# Sheet2.net
KiCad netlist of a schematic drawn in Altium Designer
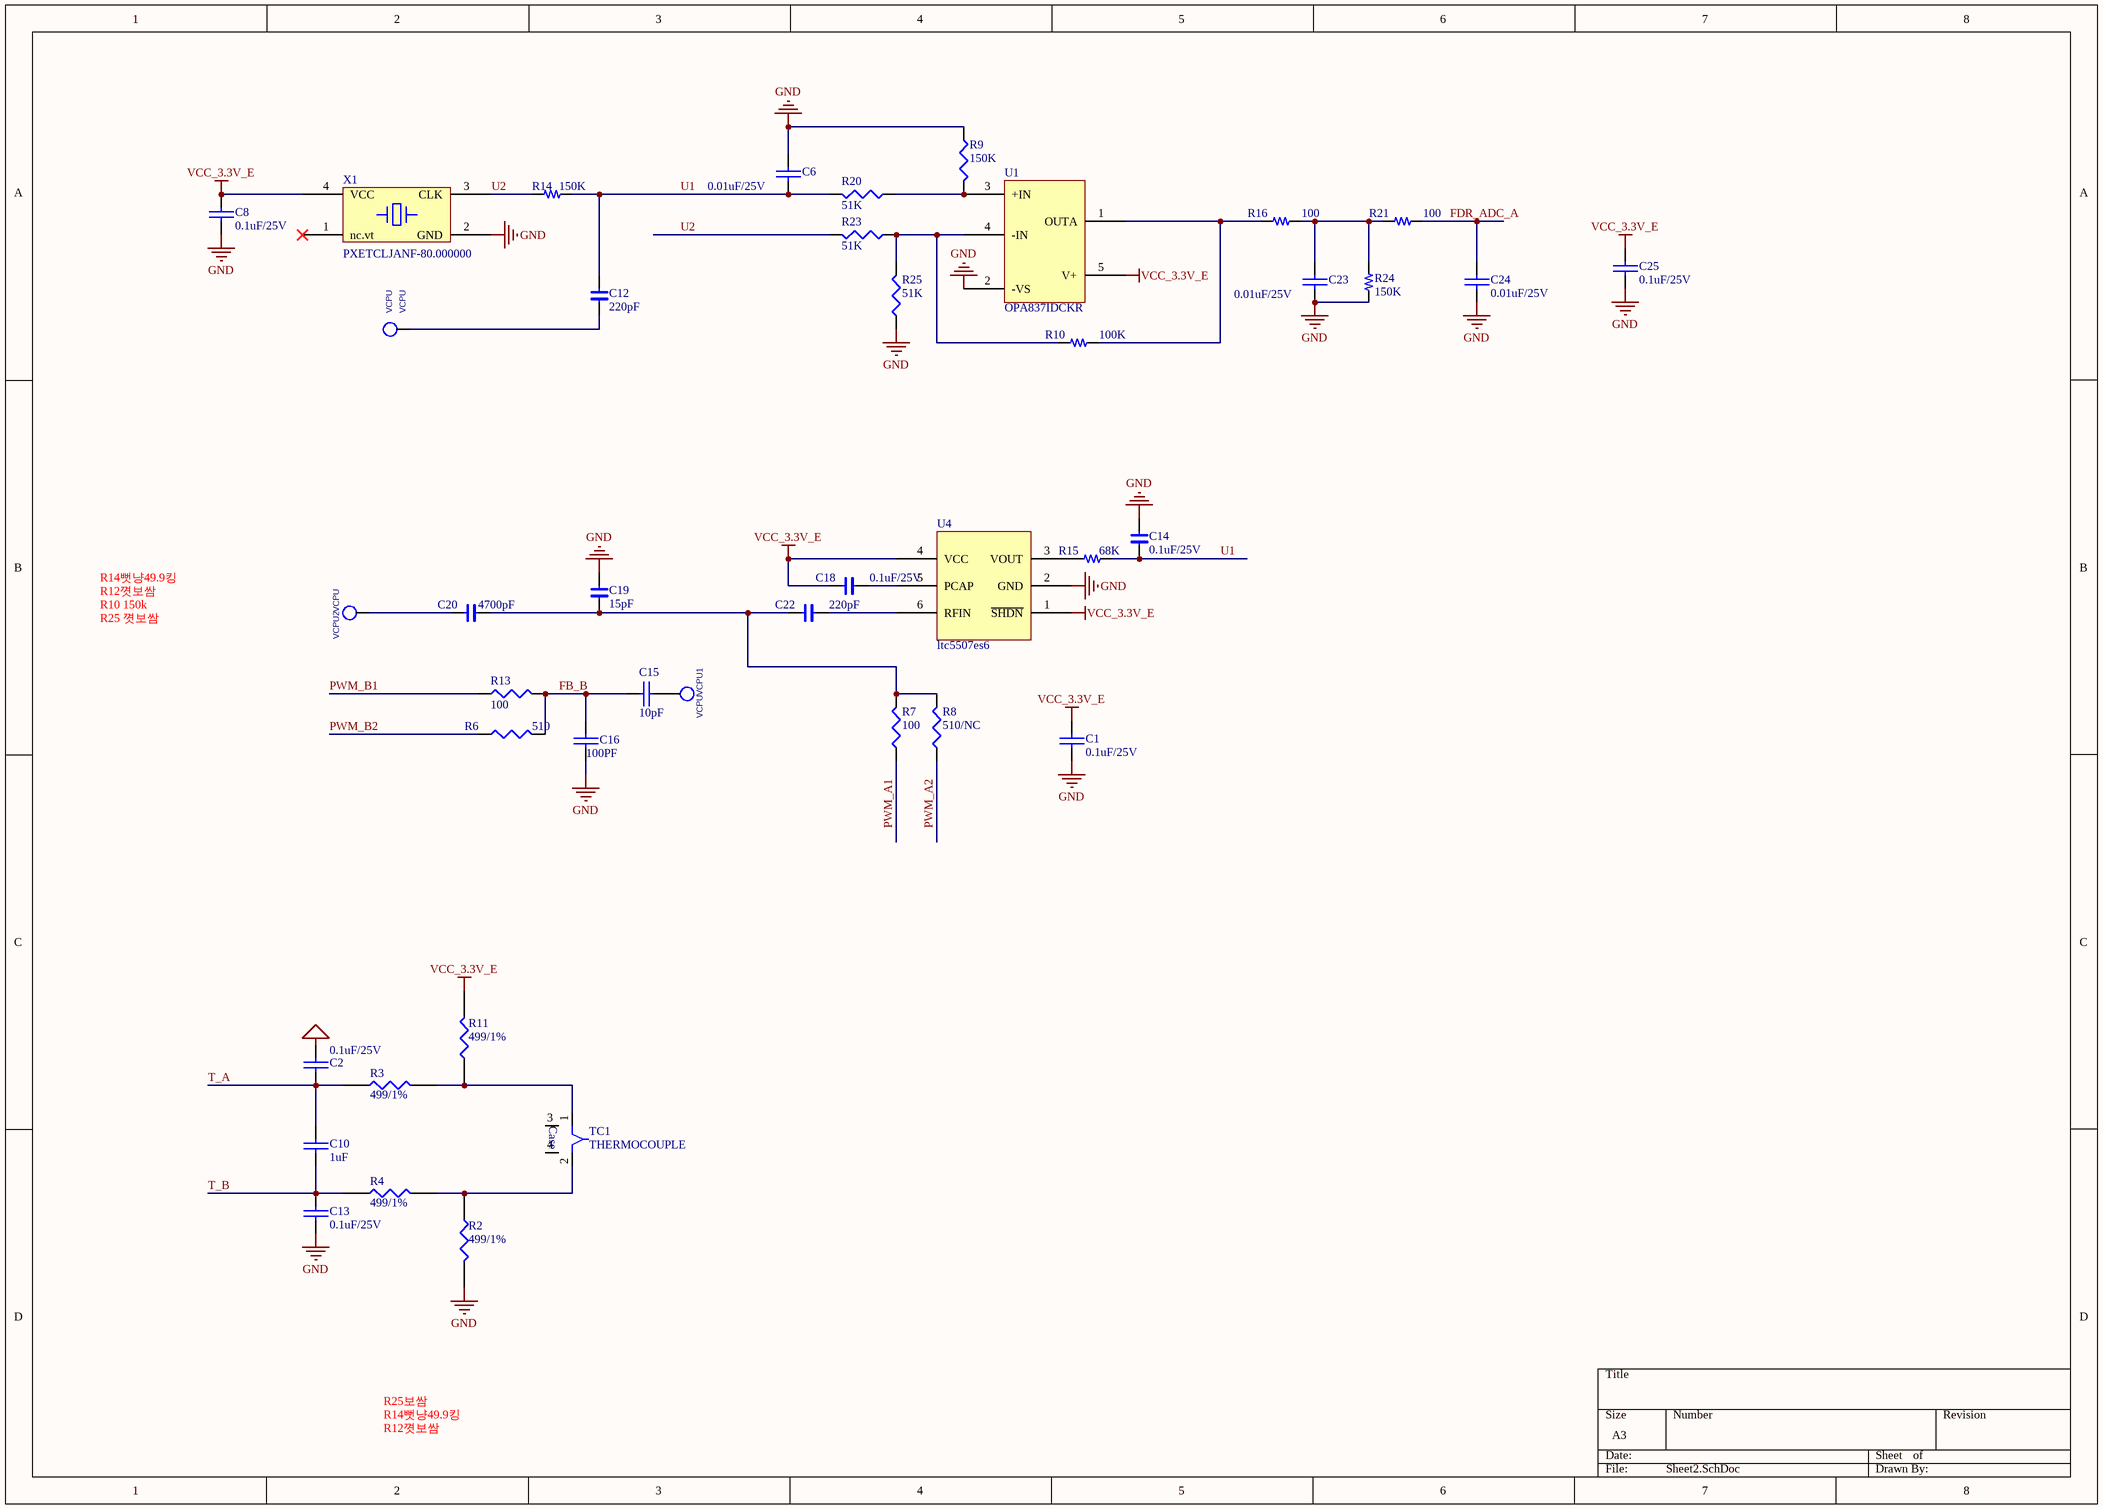
[diagram p0: Sheet2.SchDoc]

(export (version "E")
  (design (tool "Eeschema 10.0.6"))
  (components
    (comp (ref "C1")
      (value "0.1uF/25V")
      (footprint "0603C")
      (description "Capacitor")
      (libsource (lib "SM") (part "CAP"))
    )
    (comp (ref "C2")
      (value "0.1uF/25V")
      (footprint "0603c")
      (description "Capacitor")
      (libsource (lib "*") (part "CAP"))
    )
    (comp (ref "C6")
      (value "0.01uF/25V")
      (footprint "0603C")
      (description "Capacitor")
      (libsource (lib "SM") (part "CAP"))
    )
    (comp (ref "C8")
      (value "0.1uF/25V")
      (footprint "0603C")
      (description "Capacitor")
      (libsource (lib "SM") (part "CAP"))
    )
    (comp (ref "C10")
      (value "1uF")
      (footprint "0603c")
      (description "Capacitor")
      (libsource (lib "*") (part "CAP"))
    )
    (comp (ref "C12")
      (value "220pF")
      (footprint "0603C")
      (description "C")
      (libsource (lib "YxmSCH") (part "C"))
    )
    (comp (ref "C13")
      (value "0.1uF/25V")
      (footprint "0603c")
      (description "Capacitor")
      (libsource (lib "*") (part "CAP"))
    )
    (comp (ref "C14")
      (value "0.1uF/25V")
      (footprint "0603C")
      (description "C")
      (libsource (lib "YxmSCH") (part "C"))
    )
    (comp (ref "C15")
      (value "10pF")
      (footprint "0603C")
      (description "Capacitor")
      (libsource (lib "SM") (part "CAP"))
    )
    (comp (ref "C16")
      (value "100PF")
      (footprint "0603C")
      (description "Capacitor")
      (libsource (lib "SM") (part "CAP"))
    )
    (comp (ref "C18")
      (value "0.1uF/25V")
      (footprint "0603C")
      (description "C")
      (libsource (lib "YxmSCH") (part "C"))
    )
    (comp (ref "C19")
      (value "15pF")
      (footprint "0603C")
      (description "C")
      (libsource (lib "YxmSCH") (part "C"))
    )
    (comp (ref "C20")
      (value "4700pF")
      (footprint "0603C")
      (description "C")
      (libsource (lib "YxmSCH") (part "C"))
    )
    (comp (ref "C22")
      (value "220pF")
      (footprint "0603C")
      (description "C")
      (libsource (lib "YxmSCH") (part "C"))
    )
    (comp (ref "C23")
      (value "0.01uF/25V")
      (footprint "0603C")
      (description "Capacitor")
      (libsource (lib "SM") (part "CAP"))
    )
    (comp (ref "C24")
      (value "0.01uF/25V")
      (footprint "0603C")
      (description "Capacitor")
      (libsource (lib "SM") (part "CAP"))
    )
    (comp (ref "C25")
      (value "0.1uF/25V")
      (footprint "0603C")
      (description "Capacitor")
      (libsource (lib "SM") (part "CAP"))
    )
    (comp (ref "R2") (value "499/1%") (footprint "0603r") (libsource (lib "*") (part "RES1")))
    (comp (ref "R3") (value "499/1%") (footprint "0603r") (libsource (lib "*") (part "RES1")))
    (comp (ref "R4") (value "499/1%") (footprint "0603r") (libsource (lib "*") (part "RES1")))
    (comp (ref "R6")
      (value "510")
      (footprint "0603R")
      (description "Resistor")
      (fields (field (name "PUBLISHER") "Altium Limited"))
      (libsource (lib "SM") (part "Res3"))
    )
    (comp (ref "R7")
      (value "100")
      (footprint "0603R")
      (description "Resistor")
      (fields (field (name "PUBLISHER") "Altium Limited"))
      (libsource (lib "SM") (part "Res3"))
    )
    (comp (ref "R8")
      (value "510/NC")
      (footprint "0603R")
      (description "Resistor")
      (fields (field (name "PUBLISHER") "Altium Limited"))
      (libsource (lib "SM") (part "Res3"))
    )
    (comp (ref "R9")
      (value "150K")
      (footprint "0603R")
      (description "Resistor")
      (fields (field (name "PUBLISHER") "Altium Limited"))
      (libsource (lib "SM") (part "Res3"))
    )
    (comp (ref "R10")
      (value "100K")
      (footprint "0603R")
      (description "R")
      (libsource (lib "JRJ_1") (part "R"))
    )
    (comp (ref "R11") (value "499/1%") (footprint "0603r") (libsource (lib "*") (part "RES1")))
    (comp (ref "R13")
      (value "100")
      (footprint "0603R")
      (description "Resistor")
      (fields (field (name "PUBLISHER") "Altium Limited"))
      (libsource (lib "SM") (part "Res3"))
    )
    (comp (ref "R14") (value "150K") (footprint "0603r") (description "R") (libsource (lib "JRJ") (part "R")))
    (comp (ref "R15") (value "68K") (footprint "0603r") (description "R") (libsource (lib "JRJ") (part "R")))
    (comp (ref "R16")
      (value "100")
      (footprint "0603R")
      (description "R")
      (libsource (lib "JRJ_1") (part "R"))
    )
    (comp (ref "R20")
      (value "51K")
      (footprint "0603R")
      (description "Resistor")
      (fields (field (name "PUBLISHER") "Altium Limited"))
      (libsource (lib "SM") (part "Res3"))
    )
    (comp (ref "R21")
      (value "100")
      (footprint "0603R")
      (description "R")
      (libsource (lib "JRJ_1") (part "R"))
    )
    (comp (ref "R23")
      (value "51K")
      (footprint "0603R")
      (description "Resistor")
      (fields (field (name "PUBLISHER") "Altium Limited"))
      (libsource (lib "SM") (part "Res3"))
    )
    (comp (ref "R24")
      (value "150K")
      (footprint "0603R")
      (description "R")
      (libsource (lib "JRJ_1") (part "R"))
    )
    (comp (ref "R25")
      (value "51K")
      (footprint "0603R")
      (description "Resistor")
      (fields (field (name "PUBLISHER") "Altium Limited"))
      (libsource (lib "SM") (part "Res3"))
    )
    (comp (ref "TC1") (value "THERMOCOUPLE") (footprint "0603R") (libsource (lib "*") (part "THERMOCOUPLE")))
    (comp (ref "U1")
      (value "OPA837IDCKR")
      (footprint "SC70-5")
      (libsource (lib "Schlib_20110825") (part "OPA837 DCK"))
    )
    (comp (ref "U4") (value "ltc5507es6") (footprint "SOT23-6") (libsource (lib "stm32") (part "ltc5507es6")))
    (comp (ref "VCPU") (value "VCPU") (footprint "probe") (libsource (lib "*") (part "T_POINT_R")))
    (comp (ref "VCPU1") (value "VCPU") (footprint "probe") (libsource (lib "*") (part "T_POINT_R")))
    (comp (ref "VCPU2") (value "VCPU") (footprint "probe") (libsource (lib "*") (part "T_POINT_R")))
    (comp (ref "X1")
      (value "PXETCLJANF-80.000000")
      (footprint "XTAL4TN_7050")
      (libsource (lib "Y0801_V13") (part "XTAL4S"))
    )
  )
  (nets
    (net (code "1") (name "/FB_B") (class "Default")
      (node (ref "C15") (pin "1") (pinfunction "1_1") (pintype "passive"))
      (node (ref "C16") (pin "1") (pinfunction "1_1") (pintype "passive"))
      (node (ref "R13") (pin "2") (pinfunction "2_2") (pintype "passive"))
      (node (ref "R6") (pin "2") (pinfunction "2_2") (pintype "passive"))
    )
    (net (code "2") (name "/FDR_ADC_A") (class "Default")
      (node (ref "C24") (pin "2") (pinfunction "2_2") (pintype "passive"))
      (node (ref "R21") (pin "2") (pintype "passive"))
    )
    (net (code "3") (name "/PWM_A1") (class "Default")
      (node (ref "R7") (pin "1") (pinfunction "1_1") (pintype "passive"))
    )
    (net (code "4") (name "/PWM_A2") (class "Default")
      (node (ref "R8") (pin "1") (pinfunction "1_1") (pintype "passive"))
    )
    (net (code "5") (name "/PWM_B1") (class "Default")
      (node (ref "R13") (pin "1") (pinfunction "1_1") (pintype "passive"))
    )
    (net (code "6") (name "/PWM_B2") (class "Default")
      (node (ref "R6") (pin "1") (pinfunction "1_1") (pintype "passive"))
    )
    (net (code "7") (name "/T_A") (class "Default")
      (node (ref "C10") (pin "1") (pinfunction "1_1") (pintype "passive"))
      (node (ref "C2") (pin "1") (pinfunction "1_1") (pintype "passive"))
      (node (ref "R3") (pin "1") (pinfunction "1_1") (pintype "passive"))
    )
    (net (code "8") (name "/T_B") (class "Default")
      (node (ref "C10") (pin "2") (pinfunction "2_2") (pintype "passive"))
      (node (ref "C13") (pin "1") (pinfunction "1_1") (pintype "passive"))
      (node (ref "R4") (pin "1") (pinfunction "1_1") (pintype "passive"))
    )
    (net (code "9") (name "/U1") (class "Default")
      (node (ref "C12") (pin "2") (pintype "passive"))
      (node (ref "C14") (pin "1") (pintype "passive"))
      (node (ref "C6") (pin "1") (pinfunction "1_1") (pintype "passive"))
      (node (ref "R14") (pin "2") (pintype "passive"))
      (node (ref "R15") (pin "1") (pintype "passive"))
      (node (ref "R20") (pin "2") (pinfunction "2_2") (pintype "passive"))
    )
    (net (code "10") (name "/U2") (class "Default")
      (node (ref "R14") (pin "1") (pintype "passive"))
      (node (ref "R23") (pin "2") (pinfunction "2_2") (pintype "passive"))
      (node (ref "X1") (pin "3") (pinfunction "CLK_3") (pintype "passive"))
    )
    (net (code "11") (name "GND") (class "Default")
      (node (ref "C1") (pin "1") (pinfunction "1_1") (pintype "passive"))
      (node (ref "C13") (pin "2") (pinfunction "2_2") (pintype "passive"))
      (node (ref "C14") (pin "2") (pintype "passive"))
      (node (ref "C16") (pin "2") (pinfunction "2_2") (pintype "passive"))
      (node (ref "C19") (pin "2") (pintype "passive"))
      (node (ref "C2") (pin "2") (pinfunction "2_2") (pintype "passive"))
      (node (ref "C23") (pin "1") (pinfunction "1_1") (pintype "passive"))
      (node (ref "C24") (pin "1") (pinfunction "1_1") (pintype "passive"))
      (node (ref "C25") (pin "1") (pinfunction "1_1") (pintype "passive"))
      (node (ref "C6") (pin "2") (pinfunction "2_2") (pintype "passive"))
      (node (ref "C8") (pin "2") (pinfunction "2_2") (pintype "passive"))
      (node (ref "R2") (pin "2") (pinfunction "2_2") (pintype "passive"))
      (node (ref "R24") (pin "1") (pintype "passive"))
      (node (ref "R25") (pin "1") (pinfunction "1_1") (pintype "passive"))
      (node (ref "R9") (pin "1") (pinfunction "1_1") (pintype "passive"))
      (node (ref "U1") (pin "2") (pinfunction "-VS_2") (pintype "passive"))
      (node (ref "U4") (pin "2") (pinfunction "GND_2") (pintype "passive"))
      (node (ref "X1") (pin "2") (pinfunction "GND_2") (pintype "power_in"))
    )
    (net (code "12") (name "Net-(C19-Pad1)") (class "Default")
      (node (ref "C19") (pin "1") (pintype "passive"))
      (node (ref "C20") (pin "2") (pintype "passive"))
      (node (ref "C22") (pin "1") (pintype "passive"))
      (node (ref "R7") (pin "2") (pinfunction "2_2") (pintype "passive"))
      (node (ref "R8") (pin "2") (pinfunction "2_2") (pintype "passive"))
    )
    (net (code "13") (name "Net-(C23-Pad2)") (class "Default")
      (node (ref "C23") (pin "2") (pinfunction "2_2") (pintype "passive"))
      (node (ref "R16") (pin "2") (pintype "passive"))
      (node (ref "R21") (pin "1") (pintype "passive"))
      (node (ref "R24") (pin "2") (pintype "passive"))
    )
    (net (code "14") (name "Net-(R2-Pad1)") (class "Default")
      (node (ref "R2") (pin "1") (pinfunction "1_1") (pintype "passive"))
      (node (ref "R4") (pin "2") (pinfunction "2_2") (pintype "passive"))
      (node (ref "TC1") (pin "2") (pinfunction "2_2") (pintype "passive"))
    )
    (net (code "15") (name "Net-(R11-Pad1)") (class "Default")
      (node (ref "R11") (pin "1") (pinfunction "1_1") (pintype "passive"))
      (node (ref "R3") (pin "2") (pinfunction "2_2") (pintype "passive"))
      (node (ref "TC1") (pin "1") (pinfunction "1_1") (pintype "passive"))
    )
    (net (code "16") (name "Net-(U1-+IN)") (class "Default")
      (node (ref "R20") (pin "1") (pinfunction "1_1") (pintype "passive"))
      (node (ref "R9") (pin "2") (pinfunction "2_2") (pintype "passive"))
      (node (ref "U1") (pin "3") (pinfunction "+IN_3") (pintype "passive"))
    )
    (net (code "17") (name "Net-(U1--IN)") (class "Default")
      (node (ref "R10") (pin "1") (pintype "passive"))
      (node (ref "R23") (pin "1") (pinfunction "1_1") (pintype "passive"))
      (node (ref "R25") (pin "2") (pinfunction "2_2") (pintype "passive"))
      (node (ref "U1") (pin "4") (pinfunction "-IN_4") (pintype "passive"))
    )
    (net (code "18") (name "Net-(U1-OUTA)") (class "Default")
      (node (ref "R10") (pin "2") (pintype "passive"))
      (node (ref "R16") (pin "1") (pintype "passive"))
      (node (ref "U1") (pin "1") (pinfunction "OUTA_1") (pintype "passive"))
    )
    (net (code "19") (name "Net-(U4-PCAP)") (class "Default")
      (node (ref "C18") (pin "2") (pintype "passive"))
      (node (ref "U4") (pin "5") (pinfunction "PCAP_5") (pintype "passive"))
    )
    (net (code "20") (name "Net-(U4-RFIN)") (class "Default")
      (node (ref "C22") (pin "2") (pintype "passive"))
      (node (ref "U4") (pin "6") (pinfunction "RFIN_6") (pintype "passive"))
    )
    (net (code "21") (name "Net-(U4-VOUT)") (class "Default")
      (node (ref "R15") (pin "2") (pintype "passive"))
      (node (ref "U4") (pin "3") (pinfunction "VOUT_3") (pintype "passive"))
    )
    (net (code "22") (name "Net-(VCPU-TP)") (class "Default")
      (node (ref "C12") (pin "1") (pintype "passive"))
      (node (ref "VCPU") (pin "1") (pinfunction "TP_1") (pintype "passive"))
    )
    (net (code "23") (name "Net-(VCPU1-TP)") (class "Default")
      (node (ref "C15") (pin "2") (pinfunction "2_2") (pintype "passive"))
      (node (ref "VCPU1") (pin "1") (pinfunction "TP_1") (pintype "passive"))
    )
    (net (code "24") (name "Net-(VCPU2-TP)") (class "Default")
      (node (ref "C20") (pin "1") (pintype "passive"))
      (node (ref "VCPU2") (pin "1") (pinfunction "TP_1") (pintype "passive"))
    )
    (net (code "25") (name "VCC_3.3V_E") (class "Default")
      (node (ref "C1") (pin "2") (pinfunction "2_2") (pintype "passive"))
      (node (ref "C18") (pin "1") (pintype "passive"))
      (node (ref "C25") (pin "2") (pinfunction "2_2") (pintype "passive"))
      (node (ref "C8") (pin "1") (pinfunction "1_1") (pintype "passive"))
      (node (ref "R11") (pin "2") (pinfunction "2_2") (pintype "passive"))
      (node (ref "U1") (pin "5") (pinfunction "V+_5") (pintype "passive"))
      (node (ref "U4") (pin "1") (pinfunction "~{SHDN}_1") (pintype "passive"))
      (node (ref "U4") (pin "4") (pinfunction "VCC_4") (pintype "passive"))
      (node (ref "X1") (pin "4") (pinfunction "VCC_4") (pintype "power_in"))
    )
    (net (code "26") (name "unconnected-(TC1-Pad3)") (class "Default")
      (node (ref "TC1") (pin "3") (pinfunction "3_3") (pintype "passive"))
    )
    (net (code "27") (name "unconnected-(TC1-Pad4)") (class "Default")
      (node (ref "TC1") (pin "4") (pinfunction "4_4") (pintype "passive"))
    )
    (net (code "28") (name "unconnected-(X1-nc.vt-Pad1)") (class "Default")
      (node (ref "X1") (pin "1") (pinfunction "nc.vt_1") (pintype "passive+no_connect"))
    )
  )
)
